# POWER.net
KiCad netlist of a schematic drawn in Altium Designer
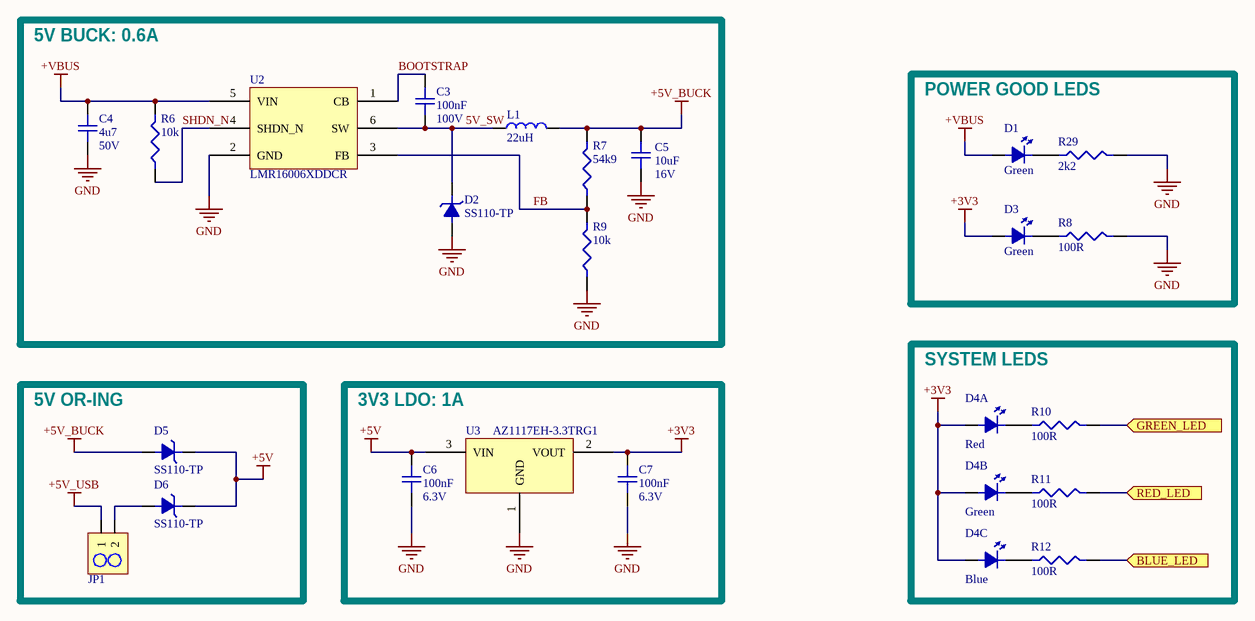
[diagram p0: POWER.SchDoc]

(export (version "E")
  (design (tool "Eeschema 10.0.6"))
  (components
    (comp (ref "C3")
      (value "100nF")
      (footprint "C0805")
      (fields
        (field (name "MANUFACTURER") "Samsung")
        (field (name "MANUFACTURER PART NUMBER") "CL21B104KCFWPNE")
        (field (name "TOLERANCE") "10%")
        (field (name "VOLTAGE RATING") "100V")
      )
      (libsource (lib "ESC_SYMBOLS") (part "CL21B104KCFWPNE"))
    )
    (comp (ref "C4")
      (value "4u7")
      (footprint "C0805")
      (description "CAP CER 4.7uF 50V X5R 10% SMD 0805 85C Embossed T/R")
      (fields
        (field (name "MANUFACTURER") "Samsung")
        (field (name "MANUFACTURER PART NUMBER") "CL21A475KBQNNNE")
        (field (name "VOLTAGE RATING") "50V")
      )
      (libsource (lib "ESC_SYMBOLS") (part "CL21A475KBQNNNE"))
    )
    (comp (ref "C5")
      (value "10uF")
      (footprint "C0805")
      (description "CAP CER 10uF 16V X5R 10% SMD 0805 85C T/R")
      (fields
        (field (name "MANUFACTURER") "Samsung")
        (field (name "MANUFACTURER PART NUMBER") "CL21A106KOQNNNE")
        (field (name "VOLTAGE RATING") "16V")
      )
      (libsource (lib "ESC_SYMBOLS") (part "CL21A106KOQNNNE"))
    )
    (comp (ref "C6")
      (value "100nF")
      (footprint "C0402")
      (description "CAP CER 0.1uF 6.3V X7R 10% SMD 0402 125C Paper T/R")
      (fields
        (field (name "MANUFACTURER") "Samsung")
        (field (name "MANUFACTURER PART NUMBER") "CL05B104KQ5NNNC")
        (field (name "VOLTAGE RATING") "6.3V")
      )
      (libsource (lib "ESC_SYMBOLS") (part "CL05B104KQ5NNNC"))
    )
    (comp (ref "C7")
      (value "100nF")
      (footprint "C0402")
      (description "CAP CER 0.1uF 6.3V X7R 10% SMD 0402 125C Paper T/R")
      (fields
        (field (name "MANUFACTURER") "Samsung")
        (field (name "MANUFACTURER PART NUMBER") "CL05B104KQ5NNNC")
        (field (name "VOLTAGE RATING") "6.3V")
      )
      (libsource (lib "ESC_SYMBOLS") (part "CL05B104KQ5NNNC"))
    )
    (comp (ref "D1")
      (value "Green")
      (footprint "LED_0603")
      (description "LED GREEN CLEAR 0603 SMD")
      (fields
        (field (name "MANUFACTURER") "Vishay Lite-On")
        (field (name "MANUFACTURER PART NUMBER") "LTST-C191KGKT")
      )
      (libsource (lib "ESC_SYMBOLS") (part "LTST-C191KGKT"))
    )
    (comp (ref "D2")
      (value "SS110-TP")
      (footprint "DO-214AA_Diode")
      (description "DIODE SCHOTTKY 100V 1A SMA")
      (fields (field (name "MANUFACTURER") "MCC"))
      (libsource (lib "ESC_SYMBOLS") (part "SS110-TP"))
    )
    (comp (ref "D3")
      (value "Green")
      (footprint "LED_0603")
      (description "LED GREEN CLEAR 0603 SMD")
      (fields
        (field (name "MANUFACTURER") "Vishay Lite-On")
        (field (name "MANUFACTURER PART NUMBER") "LTST-C191KGKT")
      )
      (libsource (lib "ESC_SYMBOLS") (part "LTST-C191KGKT"))
    )
    (comp (ref "D4")
      (value "EAST1616RGBB4")
      (footprint "LED_TRICOLOR")
      (description "LED TRICOLOR RED GREEN BLUE")
      (fields (field (name "MANUFACTURER") "Everlight"))
      (libsource (lib "ESC_SYMBOLS") (part "EAST1616RGBB4"))
    )
    (comp (ref "D5")
      (value "SS110-TP")
      (footprint "DO-214AA_Diode")
      (description "DIODE SCHOTTKY 100V 1A SMA")
      (fields (field (name "MANUFACTURER") "MCC"))
      (libsource (lib "ESC_SYMBOLS") (part "SS110-TP"))
    )
    (comp (ref "D6")
      (value "SS110-TP")
      (footprint "DO-214AA_Diode")
      (description "DIODE SCHOTTKY 100V 1A SMA")
      (fields (field (name "MANUFACTURER") "MCC"))
      (libsource (lib "ESC_SYMBOLS") (part "SS110-TP"))
    )
    (comp (ref "JP1")
      (value "952-2262-ND")
      (footprint "2PIN_HEADER")
      (description "CONN_HeaderPins2pos Headers & Wire Housings 02 SIL VERTICAL PIN HEADER TIN")
      (fields (field (name "MANUFACTURER") "Harwin") (field (name "MANUFACTURER PART NUMBER") "M20-9990246"))
      (libsource (lib "ESC_SYMBOLS") (part "M20-9990246"))
    )
    (comp (ref "L1")
      (value "22uH")
      (footprint "INDUCTOR")
      (description "INDUCTOR SHIELDED")
      (fields
        (field (name "MANUFACTURER") "Wurth Electronics")
        (field (name "MANUFACTURER PART NUMBER") "74404043220A")
      )
      (libsource (lib "ESC_SYMBOLS") (part "74404043220A"))
    )
    (comp (ref "R6")
      (value "10k")
      (footprint "R0402")
      (description "RES SMD 10K OHM 5% 1/16W 0402")
      (fields
        (field (name "MANUFACTURER") "Yageo")
        (field (name "MANUFACTURER PART NUMBER") "RC0402JR-0710KL")
      )
      (libsource (lib "ESC_SYMBOLS") (part "RC0402JR-0710KL"))
    )
    (comp (ref "R7")
      (value "54k9")
      (footprint "R0402")
      (description "RES SMD 54.9K OHM 1/10W 0402 54.9 Ohm 1% 0.1W(1/10W) ±100ppm/C Molded SMD Automotive Punched T/R")
      (fields
        (field (name "MANUFACTURER") "Panasonic")
        (field (name "MANUFACTURER PART NUMBER") "ERJ-2RKF54R9X")
      )
      (libsource (lib "ESC_SYMBOLS") (part "ERJ-2RKF54R9X"))
    )
    (comp (ref "R8")
      (value "100R")
      (footprint "R0402")
      (description "RES SMD 100 OHM 5% 1/16W 0402")
      (fields
        (field (name "MANUFACTURER") "Yageo")
        (field (name "MANUFACTURER PART NUMBER") "RC0402JR-07100RL")
      )
      (libsource (lib "ESC_SYMBOLS") (part "RC0402JR-07100RL"))
    )
    (comp (ref "R9")
      (value "10k")
      (footprint "R0402")
      (description "RES SMD 10K OHM 5% 1/16W 0402")
      (fields
        (field (name "MANUFACTURER") "Yageo")
        (field (name "MANUFACTURER PART NUMBER") "RC0402JR-0710KL")
      )
      (libsource (lib "ESC_SYMBOLS") (part "RC0402JR-0710KL"))
    )
    (comp (ref "R10")
      (value "100R")
      (footprint "R0402")
      (description "RES SMD 100 OHM 5% 1/16W 0402")
      (fields
        (field (name "MANUFACTURER") "Yageo")
        (field (name "MANUFACTURER PART NUMBER") "RC0402JR-07100RL")
      )
      (libsource (lib "ESC_SYMBOLS") (part "RC0402JR-07100RL"))
    )
    (comp (ref "R11")
      (value "100R")
      (footprint "R0402")
      (description "RES SMD 100 OHM 5% 1/16W 0402")
      (fields
        (field (name "MANUFACTURER") "Yageo")
        (field (name "MANUFACTURER PART NUMBER") "RC0402JR-07100RL")
      )
      (libsource (lib "ESC_SYMBOLS") (part "RC0402JR-07100RL"))
    )
    (comp (ref "R12")
      (value "100R")
      (footprint "R0402")
      (description "RES SMD 100 OHM 5% 1/16W 0402")
      (fields
        (field (name "MANUFACTURER") "Yageo")
        (field (name "MANUFACTURER PART NUMBER") "RC0402JR-07100RL")
      )
      (libsource (lib "ESC_SYMBOLS") (part "RC0402JR-07100RL"))
    )
    (comp (ref "R29")
      (value "2k2")
      (footprint "R0402")
      (description "RES SMD 2.2K OHM 5% 1/16W 0402")
      (fields
        (field (name "MANUFACTURER") "Yageo")
        (field (name "MANUFACTURER PART NUMBER") "RC0402JR-072K2L")
      )
      (libsource (lib "ESC_SYMBOLS") (part "RC0402JR-072K2L"))
    )
    (comp (ref "U2")
      (value "LMR16006XDDCR")
      (footprint "SOT23-6_Lead")
      (description "IC BUCK 3V3 REGULATOR 0.6A Conv DC-DC 1-OUT Step Down 4V 60V 6-Pin SOT T/R")
      (fields (field (name "MANUFACTURER") "Texas Instruments"))
      (libsource (lib "ESC_SYMBOLS") (part "LMR16006XDDCR"))
    )
    (comp (ref "U3")
      (value "AZ1117EH-3.3TRG1")
      (footprint "SOT223")
      (description "IC LDO 3V3 1A Voltage Regulators LDO BJT HiCurr")
      (fields (field (name "MANUFACTURER") "Diodes"))
      (libsource (lib "ESC_SYMBOLS") (part "AZ1117EH-3.3TRG1"))
    )
  )
  (nets
    (net (code "1") (name "+3V3") (class "Default")
      (node (ref "C7") (pin "2") (pinfunction "2_2") (pintype "passive"))
      (node (ref "D3") (pin "1") (pinfunction "1_1") (pintype "passive"))
      (node (ref "D4") (pin "4") (pinfunction "4_4") (pintype "passive"))
      (node (ref "U3") (pin "2") (pinfunction "VOUT_2") (pintype "passive"))
    )
    (net (code "2") (name "+5V") (class "Default")
      (node (ref "C6") (pin "2") (pinfunction "2_2") (pintype "passive"))
      (node (ref "D5") (pin "2") (pinfunction "2_2") (pintype "passive"))
      (node (ref "D6") (pin "2") (pinfunction "2_2") (pintype "passive"))
      (node (ref "U3") (pin "3") (pinfunction "VIN_3") (pintype "passive"))
    )
    (net (code "3") (name "+5V_BUCK") (class "Default")
      (node (ref "C5") (pin "2") (pinfunction "2_2") (pintype "passive"))
      (node (ref "D5") (pin "1") (pinfunction "1_1") (pintype "passive"))
      (node (ref "L1") (pin "2") (pinfunction "2_2") (pintype "passive"))
      (node (ref "R7") (pin "2") (pinfunction "2_2") (pintype "passive"))
    )
    (net (code "4") (name "+5V_USB") (class "Default")
      (node (ref "JP1") (pin "1") (pinfunction "1_1") (pintype "passive"))
    )
    (net (code "5") (name "+VBUS") (class "Default")
      (node (ref "C4") (pin "2") (pinfunction "2_2") (pintype "passive"))
      (node (ref "D1") (pin "1") (pinfunction "1_1") (pintype "passive"))
      (node (ref "R6") (pin "2") (pinfunction "2_2") (pintype "passive"))
      (node (ref "U2") (pin "5") (pinfunction "VIN_5") (pintype "passive"))
    )
    (net (code "6") (name "/5V_SW") (class "Default")
      (node (ref "C3") (pin "1") (pinfunction "1_1") (pintype "passive"))
      (node (ref "D2") (pin "2") (pinfunction "2_2") (pintype "passive"))
      (node (ref "L1") (pin "1") (pinfunction "1_1") (pintype "passive"))
      (node (ref "U2") (pin "6") (pinfunction "SW_6") (pintype "passive"))
    )
    (net (code "7") (name "/BLUE_LED") (class "Default")
      (node (ref "R12") (pin "2") (pinfunction "2_2") (pintype "passive"))
    )
    (net (code "8") (name "/BOOTSTRAP") (class "Default")
      (node (ref "C3") (pin "2") (pinfunction "2_2") (pintype "passive"))
      (node (ref "U2") (pin "1") (pinfunction "CB_1") (pintype "passive"))
    )
    (net (code "9") (name "/FB") (class "Default")
      (node (ref "R7") (pin "1") (pinfunction "1_1") (pintype "passive"))
      (node (ref "R9") (pin "2") (pinfunction "2_2") (pintype "passive"))
      (node (ref "U2") (pin "3") (pinfunction "FB_3") (pintype "passive"))
    )
    (net (code "10") (name "/GREEN_LED") (class "Default")
      (node (ref "R10") (pin "2") (pinfunction "2_2") (pintype "passive"))
    )
    (net (code "11") (name "/RED_LED") (class "Default")
      (node (ref "R11") (pin "2") (pinfunction "2_2") (pintype "passive"))
    )
    (net (code "12") (name "/SHDN_N") (class "Default")
      (node (ref "R6") (pin "1") (pinfunction "1_1") (pintype "passive"))
      (node (ref "U2") (pin "4") (pinfunction "SHDN_N_4") (pintype "passive"))
    )
    (net (code "13") (name "GND") (class "Default")
      (node (ref "C4") (pin "1") (pinfunction "1_1") (pintype "passive"))
      (node (ref "C5") (pin "1") (pinfunction "1_1") (pintype "passive"))
      (node (ref "C6") (pin "1") (pinfunction "1_1") (pintype "passive"))
      (node (ref "C7") (pin "1") (pinfunction "1_1") (pintype "passive"))
      (node (ref "D2") (pin "1") (pinfunction "1_1") (pintype "passive"))
      (node (ref "R29") (pin "2") (pinfunction "2_2") (pintype "passive"))
      (node (ref "R8") (pin "2") (pinfunction "2_2") (pintype "passive"))
      (node (ref "R9") (pin "1") (pinfunction "1_1") (pintype "passive"))
      (node (ref "U2") (pin "2") (pinfunction "GND_2") (pintype "passive"))
      (node (ref "U3") (pin "1") (pinfunction "GND_1") (pintype "passive"))
    )
    (net (code "14") (name "Net-(D1-Pad2)") (class "Default")
      (node (ref "D1") (pin "2") (pinfunction "2_2") (pintype "passive"))
      (node (ref "R29") (pin "1") (pinfunction "1_1") (pintype "passive"))
    )
    (net (code "15") (name "Net-(D3-Pad2)") (class "Default")
      (node (ref "D3") (pin "2") (pinfunction "2_2") (pintype "passive"))
      (node (ref "R8") (pin "1") (pinfunction "1_1") (pintype "passive"))
    )
    (net (code "16") (name "Net-(D4-Pad1)") (class "Default")
      (node (ref "D4") (pin "1") (pinfunction "1_1") (pintype "passive"))
      (node (ref "R10") (pin "1") (pinfunction "1_1") (pintype "passive"))
    )
    (net (code "17") (name "Net-(D4-Pad2)") (class "Default")
      (node (ref "D4") (pin "2") (pinfunction "2_2") (pintype "passive"))
      (node (ref "R11") (pin "1") (pinfunction "1_1") (pintype "passive"))
    )
    (net (code "18") (name "Net-(D4-Pad3)") (class "Default")
      (node (ref "D4") (pin "3") (pinfunction "3_3") (pintype "passive"))
      (node (ref "R12") (pin "1") (pinfunction "1_1") (pintype "passive"))
    )
    (net (code "19") (name "Net-(D6-Pad1)") (class "Default")
      (node (ref "D6") (pin "1") (pinfunction "1_1") (pintype "passive"))
      (node (ref "JP1") (pin "2") (pinfunction "2_2") (pintype "passive"))
    )
  )
)
